# SBH_Charger_Main.net
KiCad netlist of a schematic drawn in Altium Designer
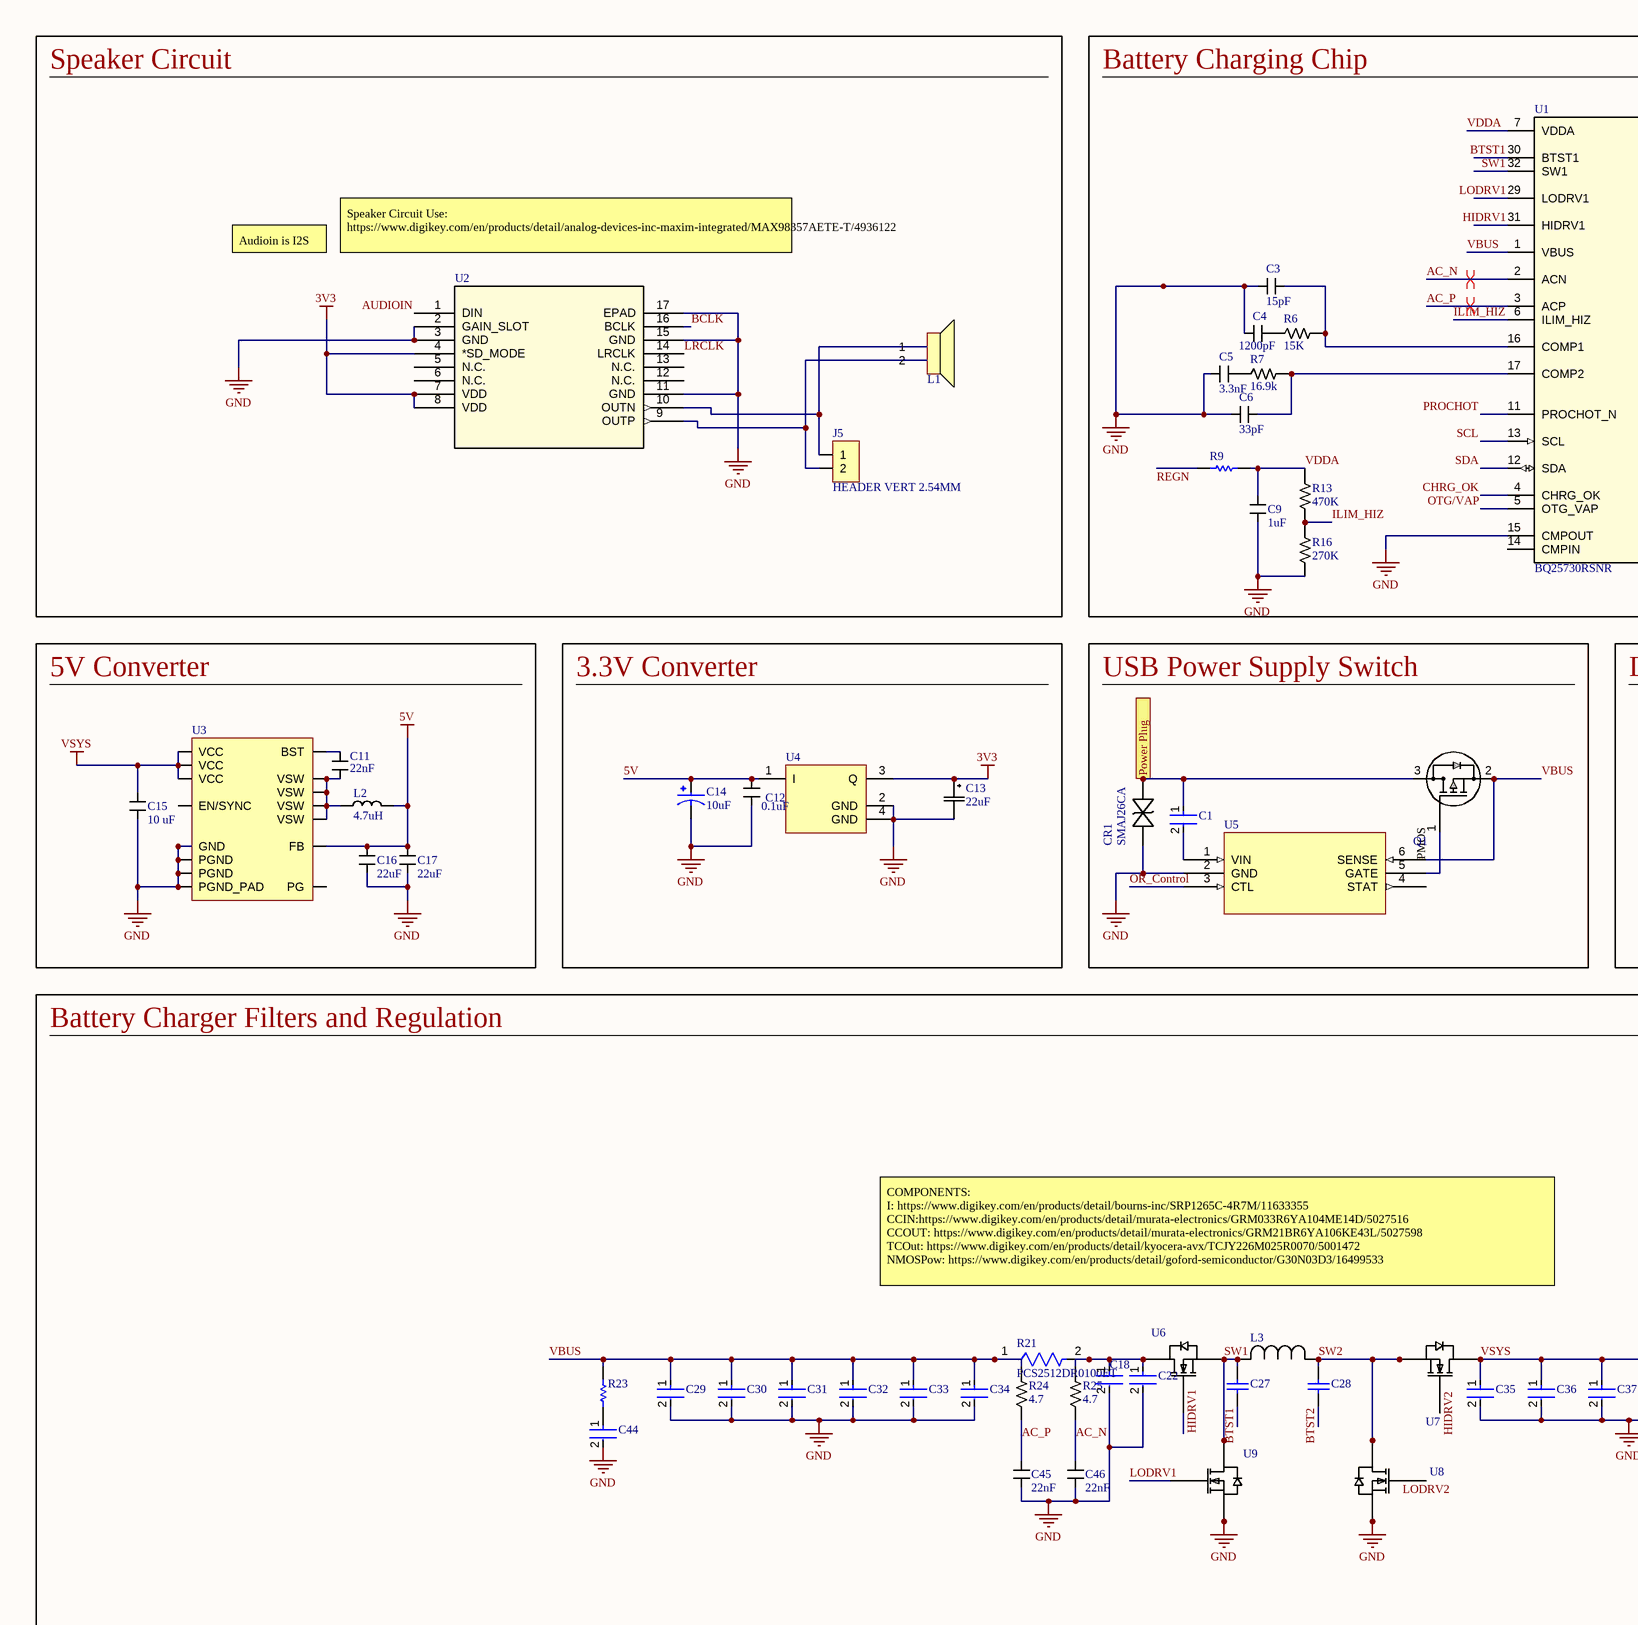
[diagram p0: SBH_Charger_Main.SchDoc, left]
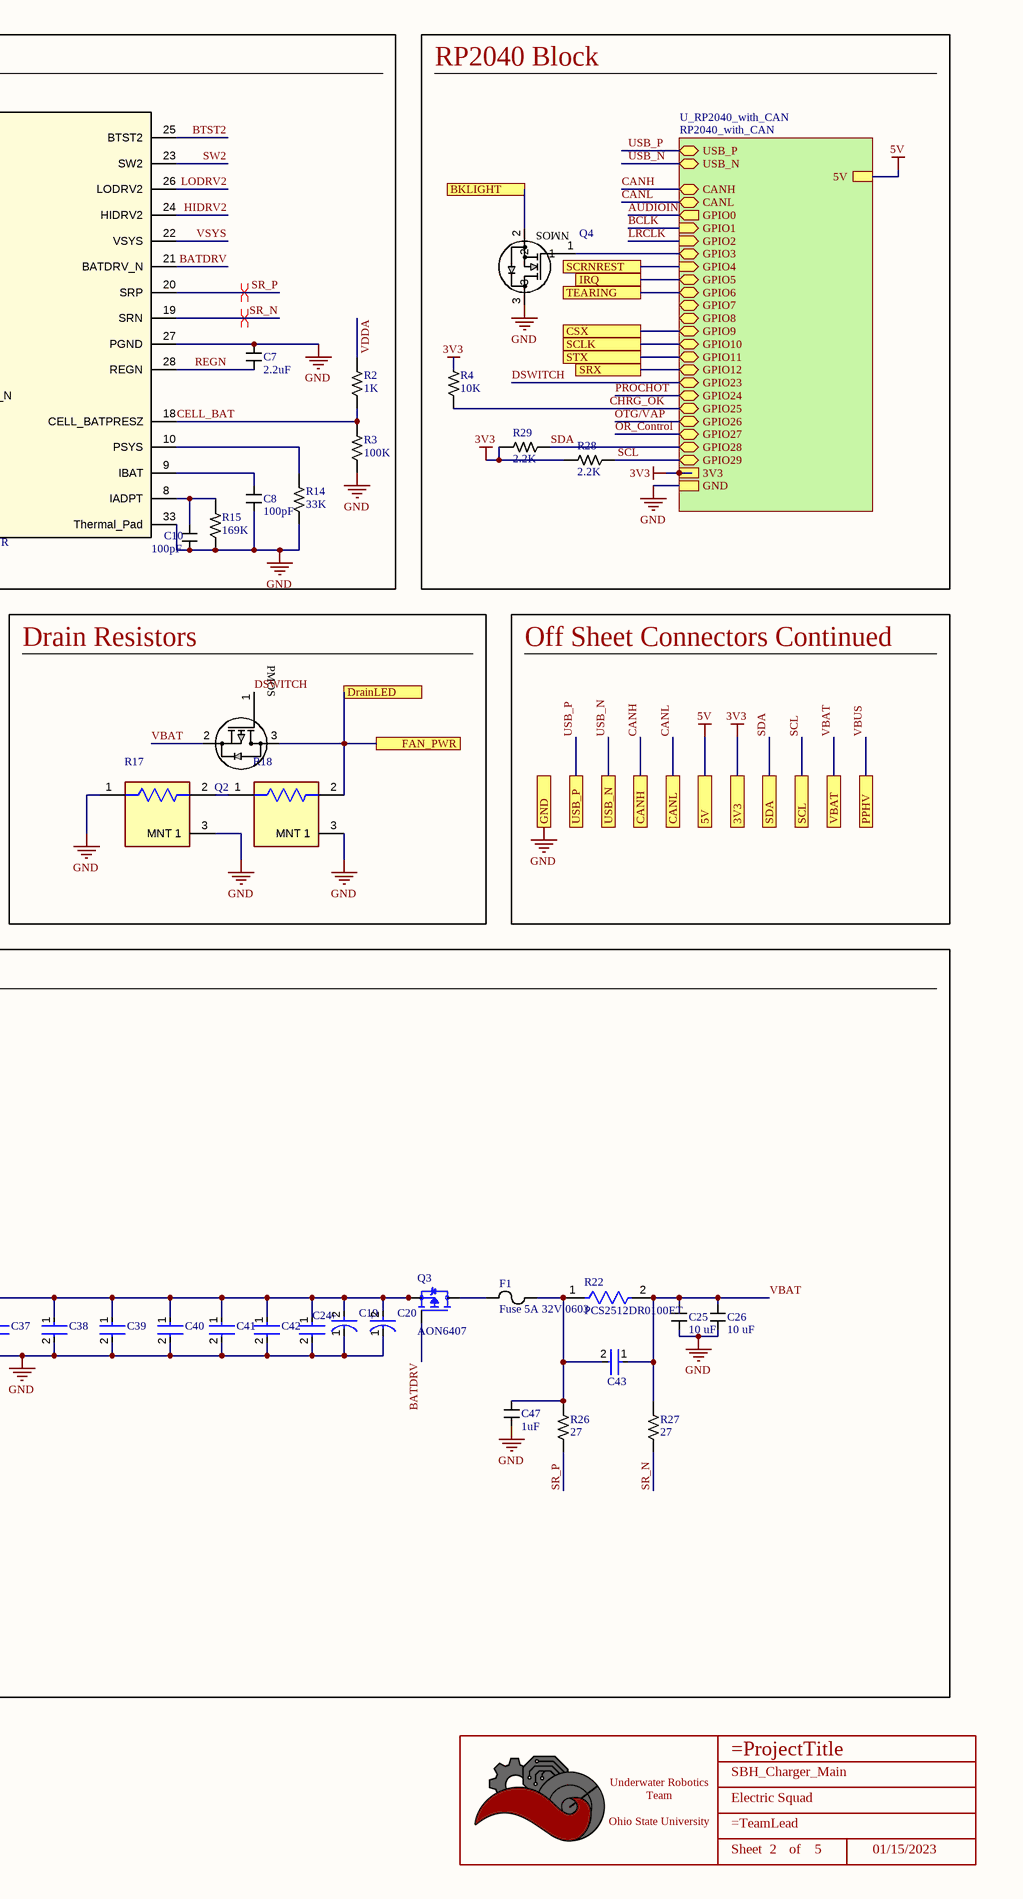
[diagram p1: SBH_Charger_Main.SchDoc, right]

(export (version "E")
  (design (tool "Eeschema 10.0.6"))
  (components
    (comp (ref "*")
      (value "Title_Block")
      (footprint "LOGO")
      (description "UWRT Schematic Title Block Template\r\n\r\nCreated June 2021, Dylan Trainor")
      (libsource (lib "UWRT") (part "Title_Block"))
    )
    (comp (ref "C1")
      (value "CC0402KRX7R9BB103")
      (footprint "CAPACITOR_0402")
      (description "CAP CER 10000PF 50V X7R 0402")
      (fields
        (field (name "OCTOPART") "https://octopart.com/cc0402krx7r9bb103-yageo-8376513")
        (field (name "MANUFACTURER") "YAGEO")
      )
      (libsource (lib "Capacitors") (part "CAP CER 0.01 UF 0402"))
    )
    (comp (ref "C3")
      (value "15pF")
      (footprint "CAPACITOR_0402")
      (description "CAP CER 15PF 50V C0G/NP0 0402")
      (fields (field (name "TOLERANCE") "+/- 5%") (field (name "VOLTAGE") "50V"))
      (libsource (lib "Capacitors") (part "CAPACITOR_0.000015uF_0402"))
    )
    (comp (ref "C4")
      (value "1200pF")
      (footprint "CAPACITOR_0402")
      (description "CAP CER 1200PF 50V X7R 0402")
      (fields (field (name "TOLERANCE") "+/- 5%") (field (name "VOLTAGE") "50V"))
      (libsource (lib "Capacitors") (part "CAPACITOR_0.0012uF_0402"))
    )
    (comp (ref "C5")
      (value "3.3nF")
      (footprint "CAPACITOR_0402")
      (description "CAP CER 3300PF 50V X7R 0402")
      (fields (field (name "TOLERANCE") "+/- 5%") (field (name "VOLTAGE") "50V"))
      (libsource (lib "Capacitors") (part "CAPACITOR_0.0033uF_0402"))
    )
    (comp (ref "C6")
      (value "33pF")
      (footprint "CAPACITOR_0402")
      (description "CAP CER 33PF 50V C0G/NP0 0402")
      (fields (field (name "TOLERANCE") "+/- 5%") (field (name "VOLTAGE") "50V"))
      (libsource (lib "Capacitors") (part "CAPACITOR_0.000033uF_0402"))
    )
    (comp (ref "C7")
      (value "2.2uF")
      (footprint "CAPACITOR_0402")
      (description "Cap 2.2uF 35V +/-10%\r\nCeramic 0402")
      (fields (field (name "TOLERANCE") "+/- 10%") (field (name "VOLTAGE") "35V"))
      (libsource (lib "Capacitors") (part "CAPACITOR_2.2uF_0402"))
    )
    (comp (ref "C8")
      (value "100pF")
      (footprint "CAPACITOR_0603")
      (description "CAP CER 100PF 50V C0G/NP0 0603")
      (fields (field (name "TOLERANCE") "+/- 5%") (field (name "VOLTAGE") "50V"))
      (libsource (lib "Capacitors") (part "CAPACITOR_0.0001uF_0603"))
    )
    (comp (ref "C9")
      (value "1uF")
      (footprint "CAPACITOR_0603")
      (description "Cap 1uF 16V +/-10%\r\nCeramic 0603")
      (fields (field (name "TOLERANCE") "+/- 10%") (field (name "VOLTAGE") "16V"))
      (libsource (lib "Capacitors") (part "CAPACITOR_1uF_0603"))
    )
    (comp (ref "C10")
      (value "100pF")
      (footprint "CAPACITOR_0603")
      (description "CAP CER 100PF 50V C0G/NP0 0603")
      (fields (field (name "TOLERANCE") "+/- 5%") (field (name "VOLTAGE") "50V"))
      (libsource (lib "Capacitors") (part "CAPACITOR_0.0001uF_0603"))
    )
    (comp (ref "C11")
      (value "22nF")
      (footprint "CAPACITOR_0402")
      (description "Cap 22nF 25V +/-10%\r\nCeramic 0402")
      (fields (field (name "TOLERANCE") "+/- 10%") (field (name "VOLTAGE") "25V"))
      (libsource (lib "Capacitors") (part "CAPACITOR_0.022uF_0402"))
    )
    (comp (ref "C12")
      (value "0.1uF")
      (footprint "CAPACITOR_0603")
      (description "Cap 100nF 25V +/-10%\r\nCeramic 0603")
      (fields (field (name "TOLERANCE") "+/- 10%") (field (name "VOLTAGE") "6.3V"))
      (libsource (lib "Capacitors") (part "CAPACITOR_0.1uF_0603_25V"))
    )
    (comp (ref "C13")
      (value "22uF")
      (footprint "PCAP_8x5.4-ELECT_NCA")
      (description "22 µF 35 V Aluminum Electrolytic Capacitors Radial, Can - SMD 1000 Hrs")
      (fields (field (name "VOLTAGE") "35V") (field (name "Comment") "22uF electrolytic 35 V"))
      (libsource (lib "Capacitors") (part "CAP ALUM 22UF 20% 35V SMD"))
    )
    (comp (ref "C14")
      (value "10uF")
      (footprint "CAP_EEHZC1J100P")
      (description "10 µF 63 V Aluminum - Polymer Capacitors Radial, Can SMD 120mOhm")
      (fields (field (name "TOLERANCE") "+/- 20%") (field (name "Comment") "10uF electrolytic 63V"))
      (libsource (lib "Capacitors") (part "CAP ALUM 10UF 20% 63V SMD"))
    )
    (comp (ref "C15")
      (value "10uF Ceramic 25V")
      (footprint "CAPACITOR_1206")
      (description "Cap 10uF 25V +/-10%\r\nCeramic 1206")
      (fields
        (field (name "TOLERANCE") "+/- 10%")
        (field (name "VOLTAGE") "25V")
        (field (name "VALUE (UF)") "10 uF")
      )
      (libsource (lib "Capacitors") (part "CAPACITOR_10uF_1206"))
    )
    (comp (ref "C16")
      (value "22uF")
      (footprint "CAPACITOR_0805")
      (description "Cap 22uF 10V +/-20% X5R\r\nCeramic 0805")
      (fields (field (name "TOLERANCE") "+/- 20%") (field (name "VOLTAGE") "10V"))
      (libsource (lib "Capacitors") (part "CAPACITOR_22uF_0805"))
    )
    (comp (ref "C17")
      (value "22uF")
      (footprint "CAPACITOR_0805")
      (description "Cap 22uF 10V +/-20% X5R\r\nCeramic 0805")
      (fields (field (name "TOLERANCE") "+/- 20%") (field (name "VOLTAGE") "10V"))
      (libsource (lib "Capacitors") (part "CAPACITOR_22uF_0805"))
    )
    (comp (ref "C18")
      (value "CC0402KRX7R9BB103")
      (footprint "FP-CC0402-MFG")
      (description "CAP CER 10000PF 50V X7R 0402")
      (fields
        (field (name "OCTOPART") "https://octopart.com/cc0402krx7r9bb103-yageo-8376513")
        (field (name "MANUFACTURER") "YAGEO")
      )
      (libsource (lib "Altium Content Vault") (part "11868f565c42a9108669ba33697ecf6"))
    )
    (comp (ref "C19")
      (value "TAJD226K035RNJ")
      (footprint "FP-TAJD-MFG")
      (description "22uF 35V  ±10% 900mΩ 2917  SMD Tantalum Capacitor")
      (fields (field (name "TOLERANCE") "10%") (field (name "VOLTAGE") "35V"))
      (libsource (lib "Altium Content Vault") (part "a00bbbee19879c290e62620ae7e47b1"))
    )
    (comp (ref "C20")
      (value "TAJD226K035RNJ")
      (footprint "FP-TAJD-MFG")
      (description "22uF 35V  ±10% 900mΩ 2917  SMD Tantalum Capacitor")
      (fields (field (name "TOLERANCE") "10%") (field (name "VOLTAGE") "35V"))
      (libsource (lib "Altium Content Vault") (part "a00bbbee19879c290e62620ae7e47b1"))
    )
    (comp (ref "C22")
      (value "C0402C102J5GACTU")
      (footprint "FP-C0402-BB-MFG")
      (description "CAP CER 1000PF 50V 5% NP0 0402")
      (fields
        (field (name "OCTOPART") "https://octopart.com/c0402c102j5gactu-kemet-9145103")
        (field (name "TOLERANCE") "0.05")
      )
      (libsource (lib "Altium Content Vault") (part "b4654b650e69147ec39a6b967a45e02"))
    )
    (comp (ref "C24")
      (value "C3216X7R1V106M160AC")
      (footprint "FP-C3216-160-0_2-IPC_C")
      (description "Multilayer Ceramic Capacitors 10uF ±20% 35V X7R SMD 1206")
      (fields (field (name "TOLERANCE") "20%"))
      (libsource (lib "Altium Content Vault") (part "11868f565c42a9108669ba33697ecf6"))
    )
    (comp (ref "C25")
      (value "10uF Ceramic 25V")
      (footprint "CAPACITOR_1206")
      (description "Cap 10uF 25V +/-10%\r\nCeramic 1206")
      (fields
        (field (name "TOLERANCE") "+/- 10%")
        (field (name "VOLTAGE") "25V")
        (field (name "VALUE (UF)") "10 uF")
      )
      (libsource (lib "Capacitors") (part "CAPACITOR_10uF_1206"))
    )
    (comp (ref "C26")
      (value "10uF Ceramic 25V")
      (footprint "CAPACITOR_1206")
      (description "Cap 10uF 25V +/-10%\r\nCeramic 1206")
      (fields
        (field (name "TOLERANCE") "+/- 10%")
        (field (name "VOLTAGE") "25V")
        (field (name "VALUE (UF)") "10 uF")
      )
      (libsource (lib "Capacitors") (part "CAPACITOR_10uF_1206"))
    )
    (comp (ref "C27")
      (value "GRM188R71H473KA61D")
      (footprint "CAPC1608X90X35ML10T15")
      (fields (field (name "MANUFACTURER") "Murata"))
      (libsource (lib "Altium Content Vault") (part "CAP"))
    )
    (comp (ref "C28")
      (value "GRM188R71H473KA61D")
      (footprint "CAPC1608X90X35ML10T15")
      (fields (field (name "MANUFACTURER") "Murata"))
      (libsource (lib "Altium Content Vault") (part "CAP"))
    )
    (comp (ref "C29")
      (value "C3216X7R1V106M160AC")
      (footprint "FP-C3216-160-0_2-IPC_C")
      (description "Multilayer Ceramic Capacitors 10uF ±20% 35V X7R SMD 1206")
      (fields (field (name "TOLERANCE") "20%"))
      (libsource (lib "Altium Content Vault") (part "11868f565c42a9108669ba33697ecf6"))
    )
    (comp (ref "C30")
      (value "C3216X7R1V106M160AC")
      (footprint "FP-C3216-160-0_2-IPC_C")
      (description "Multilayer Ceramic Capacitors 10uF ±20% 35V X7R SMD 1206")
      (fields (field (name "TOLERANCE") "20%"))
      (libsource (lib "Altium Content Vault") (part "11868f565c42a9108669ba33697ecf6"))
    )
    (comp (ref "C31")
      (value "C3216X7R1V106M160AC")
      (footprint "FP-C3216-160-0_2-IPC_C")
      (description "Multilayer Ceramic Capacitors 10uF ±20% 35V X7R SMD 1206")
      (fields (field (name "TOLERANCE") "20%"))
      (libsource (lib "Altium Content Vault") (part "11868f565c42a9108669ba33697ecf6"))
    )
    (comp (ref "C32")
      (value "C3216X7R1V106M160AC")
      (footprint "FP-C3216-160-0_2-IPC_C")
      (description "Multilayer Ceramic Capacitors 10uF ±20% 35V X7R SMD 1206")
      (fields (field (name "TOLERANCE") "20%"))
      (libsource (lib "Altium Content Vault") (part "11868f565c42a9108669ba33697ecf6"))
    )
    (comp (ref "C33")
      (value "C3216X7R1V106M160AC")
      (footprint "FP-C3216-160-0_2-IPC_C")
      (description "Multilayer Ceramic Capacitors 10uF ±20% 35V X7R SMD 1206")
      (fields (field (name "TOLERANCE") "20%"))
      (libsource (lib "Altium Content Vault") (part "11868f565c42a9108669ba33697ecf6"))
    )
    (comp (ref "C34")
      (value "C3216X7R1V106M160AC")
      (footprint "FP-C3216-160-0_2-IPC_C")
      (description "Multilayer Ceramic Capacitors 10uF ±20% 35V X7R SMD 1206")
      (fields (field (name "TOLERANCE") "20%"))
      (libsource (lib "Altium Content Vault") (part "11868f565c42a9108669ba33697ecf6"))
    )
    (comp (ref "C35")
      (value "C3216X7R1V106M160AC")
      (footprint "FP-C3216-160-0_2-IPC_C")
      (description "Multilayer Ceramic Capacitors 10uF ±20% 35V X7R SMD 1206")
      (fields (field (name "TOLERANCE") "20%"))
      (libsource (lib "Altium Content Vault") (part "11868f565c42a9108669ba33697ecf6"))
    )
    (comp (ref "C36")
      (value "C3216X7R1V106M160AC")
      (footprint "FP-C3216-160-0_2-IPC_C")
      (description "Multilayer Ceramic Capacitors 10uF ±20% 35V X7R SMD 1206")
      (fields (field (name "TOLERANCE") "20%"))
      (libsource (lib "Altium Content Vault") (part "11868f565c42a9108669ba33697ecf6"))
    )
    (comp (ref "C37")
      (value "C3216X7R1V106M160AC")
      (footprint "FP-C3216-160-0_2-IPC_C")
      (description "Multilayer Ceramic Capacitors 10uF ±20% 35V X7R SMD 1206")
      (fields (field (name "TOLERANCE") "20%"))
      (libsource (lib "Altium Content Vault") (part "11868f565c42a9108669ba33697ecf6"))
    )
    (comp (ref "C38")
      (value "C3216X7R1V106M160AC")
      (footprint "FP-C3216-160-0_2-IPC_C")
      (description "Multilayer Ceramic Capacitors 10uF ±20% 35V X7R SMD 1206")
      (fields (field (name "TOLERANCE") "20%"))
      (libsource (lib "Altium Content Vault") (part "11868f565c42a9108669ba33697ecf6"))
    )
    (comp (ref "C39")
      (value "C3216X7R1V106M160AC")
      (footprint "FP-C3216-160-0_2-IPC_C")
      (description "Multilayer Ceramic Capacitors 10uF ±20% 35V X7R SMD 1206")
      (fields (field (name "TOLERANCE") "20%"))
      (libsource (lib "Altium Content Vault") (part "11868f565c42a9108669ba33697ecf6"))
    )
    (comp (ref "C40")
      (value "C3216X7R1V106M160AC")
      (footprint "FP-C3216-160-0_2-IPC_C")
      (description "Multilayer Ceramic Capacitors 10uF ±20% 35V X7R SMD 1206")
      (fields (field (name "TOLERANCE") "20%"))
      (libsource (lib "Altium Content Vault") (part "11868f565c42a9108669ba33697ecf6"))
    )
    (comp (ref "C41")
      (value "C3216X7R1V106M160AC")
      (footprint "FP-C3216-160-0_2-IPC_C")
      (description "Multilayer Ceramic Capacitors 10uF ±20% 35V X7R SMD 1206")
      (fields (field (name "TOLERANCE") "20%"))
      (libsource (lib "Altium Content Vault") (part "11868f565c42a9108669ba33697ecf6"))
    )
    (comp (ref "C42")
      (value "C3216X7R1V106M160AC")
      (footprint "FP-C3216-160-0_2-IPC_C")
      (description "Multilayer Ceramic Capacitors 10uF ±20% 35V X7R SMD 1206")
      (fields (field (name "TOLERANCE") "20%"))
      (libsource (lib "Altium Content Vault") (part "11868f565c42a9108669ba33697ecf6"))
    )
    (comp (ref "C43")
      (value "GRM033R6YA104ME14D")
      (footprint "FP-GRM033-0_03-IPC_C")
      (description "Chip Multilayer Ceramic Capacitors for General Purpose, 0201, 0.10uF, X5R, 15%, 20%, 35V")
      (fields (field (name "TOLERANCE") "20%"))
      (libsource (lib "Capacitors") (part "CAPACITOR_0.1uF_0603_1"))
    )
    (comp (ref "C44")
      (value "UMK107AB7105KA-T")
      (footprint "FP-0603-L_1_6_0_15-W_0_8-IPC_C")
      (description "Ceramic Capacitor General Use 1uF ±10% 50V X7R 0603")
      (fields (field (name "TOLERANCE") "10%"))
      (libsource (lib "Altium Content Vault") (part "11868f565c42a9108669ba33697ecf6"))
    )
    (comp (ref "C45")
      (value "22nF")
      (footprint "CAPACITOR_0402")
      (description "Cap 22nF 25V +/-10%\r\nCeramic 0402")
      (fields (field (name "TOLERANCE") "+/- 10%") (field (name "VOLTAGE") "25V"))
      (libsource (lib "Capacitors") (part "CAPACITOR_0.022uF_0402"))
    )
    (comp (ref "C46")
      (value "22nF")
      (footprint "CAPACITOR_0402")
      (description "Cap 22nF 25V +/-10%\r\nCeramic 0402")
      (fields (field (name "TOLERANCE") "+/- 10%") (field (name "VOLTAGE") "25V"))
      (libsource (lib "Capacitors") (part "CAPACITOR_0.022uF_0402"))
    )
    (comp (ref "C47")
      (value "1uF")
      (footprint "CAPACITOR_0603")
      (description "Cap 1uF 16V +/-10%\r\nCeramic 0603")
      (fields (field (name "TOLERANCE") "+/- 10%") (field (name "VOLTAGE") "16V"))
      (libsource (lib "Capacitors") (part "CAPACITOR_1uF_0603"))
    )
    (comp (ref "CR1")
      (value "SMAJ26CA")
      (footprint "SMASeries_LTF")
      (description "TVS DIODE 26VWM 42.1VC DO214AC")
      (libsource (lib "Diodes") (part "TVS_SMAJ26CA"))
    )
    (comp (ref "F1")
      (value "Fuse 5A 32V 0603")
      (footprint "2-SMD Fuse 0603")
      (description "Pansonic ¦ 32V ¦ 5A ¦ 0603 ¦ Fast Blow")
      (fields (field (name "MANUFACTURER_PART_NUMBER") "ERB-RE5R00V"))
      (libsource (lib "Fuses") (part "ERB-RE5R00V"))
    )
    (comp (ref "J5")
      (value "HEADER VERT 2.54MM")
      (footprint "HEADER_2PIN_2.54MM")
      (description "CONN HEADER VERT 2POS 2.54MM")
      (libsource (lib "Connectors") (part "HEADER_2PIN_2.54MM"))
    )
    (comp (ref "L1")
      (value "SPEAKER_SP_1609S")
      (footprint "SPEAKER_SP-1609S")
      (description "8 Ohms General Purpose Speaker 700 mW 200 Hz ~ 5 kHz Top Rectangular")
      (libsource (lib "Inductors") (part "SPEAKER_SP_1609S"))
    )
    (comp (ref "L2")
      (value "4.7uH")
      (footprint "INDUCTOR_SLF7045")
      (description "4.7 µH Shielded Drum Core, Wirewound Inductor 2.1 A 36mOhm Max Nonstandard")
      (fields (field (name "TOLERANCE") "+/- 20%") (field (name "Comment") "4.7uH Shielded Drum Core"))
      (libsource (lib "Inductors") (part "INDUCTOR_4.7uH_SLF7045T"))
    )
    (comp (ref "L3")
      (value "SRP1770TA-3R3M")
      (footprint "INDUCTOR_SRP1770TA-3R3M_BRN")
      (description "3.3 µH Shielded Drum Core, Wirewound Inductor 28 A 3.9mOhm Max Nonstandard")
      (fields (field (name "MANUFACTURER_PART_NUMBER") "SRP1265C-4R7M"))
      (libsource (lib "Inductors") (part "INDUCTOR_3.3uH_SRP1770TA_3R3M"))
    )
    (comp (ref "Q1")
      (value "DMP3056L-7")
      (footprint "SOT-23-3")
      (description "P-Channel 30V 4.3A (Ta) 1.38W (Ta) Surface Mount SOT23")
      (libsource (lib "Transistors") (part "DMP3056L-7"))
    )
    (comp (ref "Q2")
      (value "DMP3056L-7")
      (footprint "SOT-23-3")
      (description "P-Channel 30V 4.3A (Ta) 1.38W (Ta) Surface Mount SOT23")
      (libsource (lib "Transistors") (part "DMP3056L-7"))
    )
    (comp (ref "Q3")
      (value "AON6407")
      (footprint "TRANS_AON6407")
      (description "P-Channel 30V 32A (Ta), 85A (Tc) 7.3W (Ta), 83W (Tc) Surface Mount 8-DFN (5x6)")
      (fields (field (name "DIGI-KEY_PART_NUMBER") "785-1421-1-ND") (field (name "MF") "Alpha &"))
      (libsource (lib "Transistors") (part "AON6407"))
    )
    (comp (ref "Q4")
      (value "MOSFET N-CH 30V 5.8A SOT-23-3")
      (footprint "SOT-23-3")
      (description "N-Channel 30 V 5.8A (Ta) 1.4W (Ta) Surface Mount SOT-23-3")
      (fields (field (name "MANUFACTURER _PART_NUMBER") "AO3404A"))
      (libsource (lib "Transistors") (part "AO3404A"))
    )
    (comp (ref "R2")
      (value "1k Ohm 5% 1/8W")
      (footprint "RESISTOR_0603")
      (description "RES 1k OHM 5% 1/8W 0603")
      (fields (field (name "TOLERANCE") "+/- 5%") (field (name "VALUE  (OHMS)") "1K"))
      (libsource (lib "Resistors") (part "RESISTOR_1K_0603"))
    )
    (comp (ref "R3")
      (value "100k Ohm 5% 1/8W")
      (footprint "RESISTOR_0603")
      (description "RES 100k OHM 5% 1/10W 0603")
      (fields (field (name "TOLERANCE") "+/- 5%") (field (name "VALUE  (OHMS)") "100K"))
      (libsource (lib "Resistors") (part "RESISTOR_100K_0603"))
    )
    (comp (ref "R4")
      (value "10k Ohm 5% 1/10W")
      (footprint "RESISTOR_0603")
      (description "RES 10k OHM 5% 1/10W 0603")
      (fields (field (name "TOLERANCE") "+/- 5%") (field (name "VALUE  (OHMS)") "10K"))
      (libsource (lib "Resistors") (part "RESISTOR_10K_0603"))
    )
    (comp (ref "R6")
      (value "15k Ohm 5% 1/10W")
      (footprint "RESISTOR_0603")
      (description "RES 15k OHM 5% 1/10W 0603")
      (fields (field (name "TOLERANCE") "+/- 5%") (field (name "VALUE  (OHMS)") "15K"))
      (libsource (lib "Resistors") (part "RESISTOR_15K_0603"))
    )
    (comp (ref "R7")
      (value "16.9k Ohm 1% 1/16W")
      (footprint "RESISTOR_0402")
      (description "16.9 kOhms ±1% 0.063W, 1/16W Chip Resistor 0402 (1005 Metric) Moisture Resistant Thick Film")
      (fields (field (name "TOLERANCE") "+/- 1%") (field (name "VALUE  (OHMS)") "16.9k"))
      (libsource (lib "Resistors") (part "RESISTOR_16.9K_0402"))
    )
    (comp (ref "R9")
      (value "CRCW040210R0FKEDHP")
      (footprint "RESC1005X40X25NL05T10")
      (fields (field (name "MANUFACTURER") "Vishay Dale"))
      (libsource (lib "Altium Content Vault") (part "RES"))
    )
    (comp (ref "R13")
      (value "470k Ohm 5% 1/10W")
      (footprint "RESISTOR_0603")
      (description "RES 470k OHM 5% 1/10W 0603")
      (fields (field (name "TOLERANCE") "+/- 5%") (field (name "VALUE  (OHMS)") "470K"))
      (libsource (lib "Resistors") (part "RESISTOR_470K_0603"))
    )
    (comp (ref "R14")
      (value "33k Ohm 5% 1/8W")
      (footprint "RESISTOR_0805")
      (description "RES 33k OHM 5% 1/8W 0805")
      (fields (field (name "TOLERANCE") "+/- 5%") (field (name "VALUE  (OHMS)") "33K"))
      (libsource (lib "Resistors") (part "RESISTOR_33K_0805"))
    )
    (comp (ref "R15")
      (value "169K OHM 1% 1/3W")
      (footprint "RESISTOR_0603")
      (fields (field (name "TOLERANCE") "+/- 1%") (field (name "VALUE  (OHMS)") "169K"))
      (libsource (lib "Resistors") (part "RESISTOR_169K_1%_0603"))
    )
    (comp (ref "R16")
      (value "270k Ohm 1% 1/10W")
      (footprint "RESISTOR_0603")
      (description "RES 270k OHM 1% 1/10W 0603")
      (fields (field (name "TOLERANCE") "+/- 1%") (field (name "VALUE  (OHMS)") "270K"))
      (libsource (lib "Resistors") (part "RESISTOR_270K_1%_0603"))
    )
    (comp (ref "R17")
      (value "PWR163S-25-10R0JE")
      (footprint "FP-PWR163-MFG")
      (description "RES SMD 10 OHM 5% 25W DPAK")
      (libsource (lib "Resistors") (part "PWR163S-25-10R0JE"))
    )
    (comp (ref "R18")
      (value "PWR163S-25-10R0JE")
      (footprint "FP-PWR163-MFG")
      (description "RES SMD 10 OHM 5% 25W DPAK")
      (libsource (lib "Resistors") (part "PWR163S-25-10R0JE"))
    )
    (comp (ref "R21")
      (value "PCS2512DR0100ET")
      (footprint "FP-PCS2512-MFG")
      (description "2W 0.010 OHMS 0.5% 2512")
      (fields
        (field (name "OCTOPART") "https://octopart.com/pcs2512dr0100et-ohmite-106082038")
        (field (name "TOLERANCE") "0.%")
      )
      (libsource (lib "Altium Content Vault") (part "1029c3af85768c4190bb7ad29bc67b5"))
    )
    (comp (ref "R22")
      (value "PCS2512DR0100ET")
      (footprint "FP-PCS2512-MFG")
      (description "2W 0.010 OHMS 0.5% 2512")
      (fields
        (field (name "OCTOPART") "https://octopart.com/pcs2512dr0100et-ohmite-106082038")
        (field (name "TOLERANCE") "0.%")
      )
      (libsource (lib "Altium Content Vault") (part "1029c3af85768c4190bb7ad29bc67b5"))
    )
    (comp (ref "R23")
      (value "CRCW06032R20FKEA")
      (footprint "RESC1609X50X30ML10T20")
      (fields (field (name "MANUFACTURER") "Vishay Dale"))
      (libsource (lib "Altium Content Vault") (part "RES"))
    )
    (comp (ref "R24")
      (value "4.7 Ohm 5% 1/8W")
      (footprint "RESISTOR_0603")
      (description "RES 4.7 OHM 5% 1/8W 0603")
      (fields (field (name "TOLERANCE") "+/- 5%") (field (name "VALUE  (OHMS)") "4.7"))
      (libsource (lib "Resistors") (part "RESISTOR_4.7_0603"))
    )
    (comp (ref "R25")
      (value "4.7 Ohm 5% 1/8W")
      (footprint "RESISTOR_0603")
      (description "RES 4.7 OHM 5% 1/8W 0603")
      (fields (field (name "TOLERANCE") "+/- 5%") (field (name "VALUE  (OHMS)") "4.7"))
      (libsource (lib "Resistors") (part "RESISTOR_4.7_0603"))
    )
    (comp (ref "R26")
      (value "27 Ohm 5% 1/8W")
      (footprint "RESISTOR_0603")
      (description "RES 27 OHM 5% 1/8W 0603")
      (fields (field (name "TOLERANCE") "+/- 5%") (field (name "VALUE  (OHMS)") "27"))
      (libsource (lib "Resistors") (part "RESISTOR_27_0603"))
    )
    (comp (ref "R27")
      (value "27 Ohm 5% 1/8W")
      (footprint "RESISTOR_0603")
      (description "RES 27 OHM 5% 1/8W 0603")
      (fields (field (name "TOLERANCE") "+/- 5%") (field (name "VALUE  (OHMS)") "27"))
      (libsource (lib "Resistors") (part "RESISTOR_27_0603"))
    )
    (comp (ref "R28")
      (value "2.2k Ohm 1% 1/16W")
      (footprint "RESISTOR_0402")
      (description "RES 2.2K OHM 1% 1/16W 0402")
      (fields (field (name "TOLERANCE") "+/- 1%") (field (name "VALUE  (OHMS)") "2.2K"))
      (libsource (lib "Resistors") (part "RESISTOR_2.2K_0402_1"))
    )
    (comp (ref "R29")
      (value "2.2k Ohm 1% 1/16W")
      (footprint "RESISTOR_0402")
      (description "RES 2.2K OHM 1% 1/16W 0402")
      (fields (field (name "TOLERANCE") "+/- 1%") (field (name "VALUE  (OHMS)") "2.2K"))
      (libsource (lib "Resistors") (part "RESISTOR_2.2K_0402_1"))
    )
    (comp (ref "U1")
      (value "BQ25730RSNR")
      (footprint "RSN0032B-IPC_B")
      (description "I2C 1 TO 5 CELL, 2-V, NARROW VDC, Charger IC Multi-Chemistry 32-QFN (4x4)")
      (libsource (lib "Integrated Circuits") (part "BQ25730RSNR"))
    )
    (comp (ref "U2")
      (value "MAX98357AETE+T")
      (footprint "TQFN-16")
      (description "Audio Amplifiers Digital Input Class D Amplifier")
      (libsource (lib "Integrated Circuits") (part "MAX98357AETE+T"))
    )
    (comp (ref "U3")
      (value "REG BUCK 5V 1A")
      (footprint "QFN-16 (3x3)")
      (description "Buck Switching Regulator IC Positive Fixed 5V 1 Output 1A 16-VFQFN Exposed Pad")
      (libsource (lib "Integrated Circuits") (part "TS30041-M050QFNR"))
    )
    (comp (ref "U4")
      (value "TLE42744GS V33")
      (footprint "INF-PG-SOT223_SC-73_N")
      (fields (field (name "MANUFACTURER") "Infineon"))
      (libsource (lib "Integrated Circuits") (part "CMP-1109-00085-1"))
    )
    (comp (ref "U5")
      (value "LTC4412ES6TRPBF")
      (footprint "TSOT-23_S6")
      (description "OR Controller Source Selector Switch P-Channel 2:1 TSOT-23-6")
      (fields (field (name "MP") "LTC4412ES6#TRPBF") (field (name "MF") "Analog Devices"))
      (libsource (lib "Integrated Circuits") (part "LTC4412ES6TRPBF"))
    )
    (comp (ref "U6")
      (value "G30N03D3")
      (footprint "DNH0008A_NV")
      (description "N-Channel 30 V 30A 24W Surface Mount 8-DFN (3.15x3.05)")
      (libsource (lib "Transistors") (part "G30N03D3"))
    )
    (comp (ref "U7")
      (value "G30N03D3")
      (footprint "DNH0008A_NV")
      (description "N-Channel 30 V 30A 24W Surface Mount 8-DFN (3.15x3.05)")
      (libsource (lib "Transistors") (part "G30N03D3"))
    )
    (comp (ref "U8")
      (value "G30N03D3")
      (footprint "DNH0008A_NV")
      (description "N-Channel 30 V 30A 24W Surface Mount 8-DFN (3.15x3.05)")
      (libsource (lib "Transistors") (part "G30N03D3"))
    )
    (comp (ref "U9")
      (value "G30N03D3")
      (footprint "DNH0008A_NV")
      (description "N-Channel 30 V 30A 24W Surface Mount 8-DFN (3.15x3.05)")
      (libsource (lib "Transistors") (part "G30N03D3"))
    )
  )
  (nets
    (net (code "2") (name "/AC_N") (class "Default")
      (node (ref "C46") (pin "1") (pinfunction "1_1") (pintype "passive"))
      (node (ref "R25") (pin "2") (pinfunction "2_2") (pintype "passive"))
      (node (ref "U1") (pin "2") (pinfunction "ACN_2") (pintype "passive"))
    )
    (net (code "3") (name "/AC_P") (class "Default")
      (node (ref "C45") (pin "1") (pinfunction "1_1") (pintype "passive"))
      (node (ref "R24") (pin "2") (pinfunction "2_2") (pintype "passive"))
      (node (ref "U1") (pin "3") (pinfunction "ACP_3") (pintype "passive"))
    )
    (net (code "4") (name "/AUDIOIN") (class "Default")
      (node (ref "U2") (pin "1") (pinfunction "DIN_1") (pintype "passive"))
    )
    (net (code "5") (name "/BATDRV") (class "Default")
      (node (ref "Q3") (pin "4") (pinfunction "G_4") (pintype "passive"))
      (node (ref "U1") (pin "21") (pinfunction "BATDRV_N_21") (pintype "passive"))
    )
    (net (code "6") (name "/BCLK") (class "Default")
      (node (ref "U2") (pin "16") (pinfunction "BCLK_16") (pintype "passive"))
    )
    (net (code "7") (name "/BKLIGHT") (class "Default")
      (node (ref "Q4") (pin "2") (pinfunction "2_2") (pintype "passive"))
    )
    (net (code "8") (name "/BTST1") (class "Default")
      (node (ref "C27") (pin "1") (pinfunction "1_1") (pintype "passive"))
      (node (ref "U1") (pin "30") (pinfunction "BTST1_30") (pintype "passive"))
    )
    (net (code "9") (name "/BTST2") (class "Default")
      (node (ref "C28") (pin "1") (pinfunction "1_1") (pintype "passive"))
      (node (ref "U1") (pin "25") (pinfunction "BTST2_25") (pintype "passive"))
    )
    (net (code "12") (name "/CELL_BAT") (class "Default")
      (node (ref "R2") (pin "2") (pinfunction "2_2") (pintype "passive"))
      (node (ref "R3") (pin "1") (pinfunction "1_1") (pintype "passive"))
      (node (ref "U1") (pin "18") (pinfunction "CELL_BATPRESZ_18") (pintype "passive"))
    )
    (net (code "13") (name "/CHRG_OK") (class "Default")
      (node (ref "R4") (pin "2") (pinfunction "2_2") (pintype "passive"))
      (node (ref "U1") (pin "4") (pinfunction "CHRG_OK_4") (pintype "passive"))
    )
    (net (code "15") (name "/DSWITCH") (class "Default")
      (node (ref "Q2") (pin "1") (pinfunction "1_1") (pintype "passive"))
    )
    (net (code "16") (name "/DrainLED") (class "Default")
      (node (ref "Q2") (pin "3") (pinfunction "3_3") (pintype "passive"))
      (node (ref "R18") (pin "2") (pinfunction "2_2") (pintype "passive"))
    )
    (net (code "17") (name "/GPIO3") (class "Default")
      (node (ref "Q4") (pin "1") (pinfunction "1_1") (pintype "passive"))
    )
    (net (code "20") (name "/HIDRV1") (class "Default")
      (node (ref "U1") (pin "31") (pinfunction "HIDRV1_31") (pintype "passive"))
      (node (ref "U6") (pin "4") (pinfunction "G_4") (pintype "passive"))
    )
    (net (code "21") (name "/HIDRV2") (class "Default")
      (node (ref "U1") (pin "24") (pinfunction "HIDRV2_24") (pintype "passive"))
      (node (ref "U7") (pin "4") (pinfunction "G_4") (pintype "passive"))
    )
    (net (code "22") (name "/ILIM_HIZ") (class "Default")
      (node (ref "R13") (pin "2") (pinfunction "2_2") (pintype "passive"))
      (node (ref "R16") (pin "1") (pinfunction "1_1") (pintype "passive"))
      (node (ref "U1") (pin "6") (pinfunction "ILIM_HIZ_6") (pintype "passive"))
    )
    (net (code "24") (name "/LODRV1") (class "Default")
      (node (ref "U1") (pin "29") (pinfunction "LODRV1_29") (pintype "passive"))
      (node (ref "U9") (pin "4") (pinfunction "G_4") (pintype "passive"))
    )
    (net (code "25") (name "/LODRV2") (class "Default")
      (node (ref "U1") (pin "26") (pinfunction "LODRV2_26") (pintype "passive"))
      (node (ref "U8") (pin "4") (pinfunction "G_4") (pintype "passive"))
    )
    (net (code "26") (name "/LRCLK") (class "Default")
      (node (ref "U2") (pin "14") (pinfunction "LRCLK_14") (pintype "passive"))
    )
    (net (code "27") (name "/OR_Control") (class "Default")
      (node (ref "U5") (pin "3") (pinfunction "CTL_3") (pintype "input"))
    )
    (net (code "28") (name "/OTG{slash}VAP") (class "Default")
      (node (ref "U1") (pin "5") (pinfunction "OTG_VAP_5") (pintype "passive"))
    )
    (net (code "29") (name "/PROCHOT") (class "Default")
      (node (ref "U1") (pin "11") (pinfunction "PROCHOT_N_11") (pintype "passive"))
    )
    (net (code "30") (name "/Power Plug") (class "Default")
      (node (ref "C1") (pin "1") (pinfunction "1_1") (pintype "passive"))
      (node (ref "CR1") (pin "1") (pinfunction "1_1") (pintype "passive"))
      (node (ref "Q1") (pin "3") (pinfunction "3_3") (pintype "passive"))
    )
    (net (code "31") (name "/REGN") (class "Default")
      (node (ref "C7") (pin "2") (pinfunction "2_2") (pintype "passive"))
      (node (ref "R9") (pin "1") (pinfunction "1_1") (pintype "passive"))
      (node (ref "U1") (pin "28") (pinfunction "REGN_28") (pintype "passive"))
    )
    (net (code "32") (name "/SCL") (class "Default")
      (node (ref "R28") (pin "2") (pinfunction "2_2") (pintype "passive"))
      (node (ref "U1") (pin "13") (pinfunction "SCL_13") (pintype "input"))
    )
    (net (code "35") (name "/SDA") (class "Default")
      (node (ref "R29") (pin "2") (pinfunction "2_2") (pintype "passive"))
      (node (ref "U1") (pin "12") (pinfunction "SDA_12") (pintype "bidirectional"))
    )
    (net (code "37") (name "/SR_N") (class "Default")
      (node (ref "R27") (pin "2") (pinfunction "2_2") (pintype "passive"))
      (node (ref "U1") (pin "19") (pinfunction "SRN_19") (pintype "passive"))
    )
    (net (code "38") (name "/SR_P") (class "Default")
      (node (ref "R26") (pin "2") (pinfunction "2_2") (pintype "passive"))
      (node (ref "U1") (pin "20") (pinfunction "SRP_20") (pintype "passive"))
    )
    (net (code "40") (name "/SW1") (class "Default")
      (node (ref "C27") (pin "2") (pinfunction "2_2") (pintype "passive"))
      (node (ref "L3") (pin "2") (pinfunction "2_2") (pintype "passive"))
      (node (ref "U1") (pin "32") (pinfunction "SW1_32") (pintype "passive"))
      (node (ref "U6") (pin "1") (pinfunction "S_1") (pintype "passive"))
      (node (ref "U6") (pin "2") (pinfunction "S_2") (pintype "passive"))
      (node (ref "U6") (pin "3") (pinfunction "S_3") (pintype "passive"))
      (node (ref "U9") (pin "5") (pinfunction "D_5") (pintype "passive"))
      (node (ref "U9") (pin "6") (pinfunction "D_6") (pintype "passive"))
      (node (ref "U9") (pin "7") (pinfunction "D_7") (pintype "passive"))
      (node (ref "U9") (pin "8") (pinfunction "D_8") (pintype "passive"))
      (node (ref "U9") (pin "9") (pinfunction "D_9") (pintype "passive"))
    )
    (net (code "41") (name "/SW2") (class "Default")
      (node (ref "C28") (pin "2") (pinfunction "2_2") (pintype "passive"))
      (node (ref "L3") (pin "1") (pinfunction "1_1") (pintype "passive"))
      (node (ref "U1") (pin "23") (pinfunction "SW2_23") (pintype "passive"))
      (node (ref "U7") (pin "1") (pinfunction "S_1") (pintype "passive"))
      (node (ref "U7") (pin "2") (pinfunction "S_2") (pintype "passive"))
      (node (ref "U7") (pin "3") (pinfunction "S_3") (pintype "passive"))
      (node (ref "U8") (pin "5") (pinfunction "D_5") (pintype "passive"))
      (node (ref "U8") (pin "6") (pinfunction "D_6") (pintype "passive"))
      (node (ref "U8") (pin "7") (pinfunction "D_7") (pintype "passive"))
      (node (ref "U8") (pin "8") (pinfunction "D_8") (pintype "passive"))
      (node (ref "U8") (pin "9") (pinfunction "D_9") (pintype "passive"))
    )
    (net (code "45") (name "/VBAT") (class "Default")
      (node (ref "C25") (pin "1") (pinfunction "1_1") (pintype "passive"))
      (node (ref "C26") (pin "1") (pinfunction "1_1") (pintype "passive"))
      (node (ref "C43") (pin "1") (pinfunction "1_1") (pintype "passive"))
      (node (ref "Q2") (pin "2") (pinfunction "2_2") (pintype "passive"))
      (node (ref "R22") (pin "2") (pinfunction "2_2") (pintype "passive"))
      (node (ref "R27") (pin "1") (pinfunction "1_1") (pintype "passive"))
    )
    (net (code "46") (name "/VBUS") (class "Default")
      (node (ref "C29") (pin "1") (pinfunction "1_1") (pintype "passive"))
      (node (ref "C30") (pin "1") (pinfunction "1_1") (pintype "passive"))
      (node (ref "C31") (pin "1") (pinfunction "1_1") (pintype "passive"))
      (node (ref "C32") (pin "1") (pinfunction "1_1") (pintype "passive"))
      (node (ref "C33") (pin "1") (pinfunction "1_1") (pintype "passive"))
      (node (ref "C34") (pin "1") (pinfunction "1_1") (pintype "passive"))
      (node (ref "Q1") (pin "2") (pinfunction "2_2") (pintype "passive"))
      (node (ref "R21") (pin "1") (pinfunction "1_1") (pintype "passive"))
      (node (ref "R23") (pin "2") (pinfunction "2_2") (pintype "passive"))
      (node (ref "R24") (pin "1") (pinfunction "1_1") (pintype "passive"))
      (node (ref "U1") (pin "1") (pinfunction "VBUS_1") (pintype "power_in"))
      (node (ref "U5") (pin "6") (pinfunction "SENSE_6") (pintype "input"))
    )
    (net (code "47") (name "/VDDA") (class "Default")
      (node (ref "C9") (pin "1") (pinfunction "1_1") (pintype "passive"))
      (node (ref "R13") (pin "1") (pinfunction "1_1") (pintype "passive"))
      (node (ref "R2") (pin "1") (pinfunction "1_1") (pintype "passive"))
      (node (ref "R9") (pin "2") (pinfunction "2_2") (pintype "passive"))
      (node (ref "U1") (pin "7") (pinfunction "VDDA_7") (pintype "power_in"))
    )
    (net (code "48") (name "3V3") (class "Default")
      (node (ref "C13") (pin "1") (pinfunction "1_1") (pintype "passive"))
      (node (ref "R28") (pin "1") (pinfunction "1_1") (pintype "passive"))
      (node (ref "R29") (pin "1") (pinfunction "1_1") (pintype "passive"))
      (node (ref "R4") (pin "1") (pinfunction "1_1") (pintype "passive"))
      (node (ref "U2") (pin "4") (pinfunction "*SD_MODE_4") (pintype "passive"))
      (node (ref "U2") (pin "7") (pinfunction "VDD_7") (pintype "power_in"))
      (node (ref "U2") (pin "8") (pinfunction "VDD_8") (pintype "power_in"))
      (node (ref "U4") (pin "3") (pinfunction "Q_3") (pintype "power_in"))
    )
    (net (code "49") (name "5V") (class "Default")
      (node (ref "C12") (pin "1") (pinfunction "1_1") (pintype "passive"))
      (node (ref "C14") (pin "1") (pinfunction "1_1") (pintype "passive"))
      (node (ref "C16") (pin "1") (pinfunction "1_1") (pintype "passive"))
      (node (ref "C17") (pin "1") (pinfunction "1_1") (pintype "passive"))
      (node (ref "L2") (pin "1") (pinfunction "1_1") (pintype "passive"))
      (node (ref "U3") (pin "5") (pinfunction "FB_5") (pintype "passive"))
      (node (ref "U4") (pin "1") (pinfunction "I_1") (pintype "power_in"))
    )
    (net (code "50") (name "GND") (class "Default")
      (node (ref "C10") (pin "2") (pinfunction "2_2") (pintype "passive"))
      (node (ref "C12") (pin "2") (pinfunction "2_2") (pintype "passive"))
      (node (ref "C13") (pin "2") (pinfunction "2_2") (pintype "passive"))
      (node (ref "C14") (pin "2") (pinfunction "2_2") (pintype "passive"))
      (node (ref "C15") (pin "2") (pinfunction "2_2") (pintype "passive"))
      (node (ref "C16") (pin "2") (pinfunction "2_2") (pintype "passive"))
      (node (ref "C17") (pin "2") (pinfunction "2_2") (pintype "passive"))
      (node (ref "C18") (pin "2") (pinfunction "2_2") (pintype "passive"))
      (node (ref "C19") (pin "1") (pinfunction "C_1") (pintype "passive"))
      (node (ref "C20") (pin "1") (pinfunction "C_1") (pintype "passive"))
      (node (ref "C22") (pin "2") (pinfunction "2_2") (pintype "passive"))
      (node (ref "C24") (pin "2") (pinfunction "2_2") (pintype "passive"))
      (node (ref "C25") (pin "2") (pinfunction "2_2") (pintype "passive"))
      (node (ref "C26") (pin "2") (pinfunction "2_2") (pintype "passive"))
      (node (ref "C29") (pin "2") (pinfunction "2_2") (pintype "passive"))
      (node (ref "C3") (pin "2") (pinfunction "2_2") (pintype "passive"))
      (node (ref "C30") (pin "2") (pinfunction "2_2") (pintype "passive"))
      (node (ref "C31") (pin "2") (pinfunction "2_2") (pintype "passive"))
      (node (ref "C32") (pin "2") (pinfunction "2_2") (pintype "passive"))
      (node (ref "C33") (pin "2") (pinfunction "2_2") (pintype "passive"))
      (node (ref "C34") (pin "2") (pinfunction "2_2") (pintype "passive"))
      (node (ref "C35") (pin "2") (pinfunction "2_2") (pintype "passive"))
      (node (ref "C36") (pin "2") (pinfunction "2_2") (pintype "passive"))
      (node (ref "C37") (pin "2") (pinfunction "2_2") (pintype "passive"))
      (node (ref "C38") (pin "2") (pinfunction "2_2") (pintype "passive"))
      (node (ref "C39") (pin "2") (pinfunction "2_2") (pintype "passive"))
      (node (ref "C4") (pin "2") (pinfunction "2_2") (pintype "passive"))
      (node (ref "C40") (pin "2") (pinfunction "2_2") (pintype "passive"))
      (node (ref "C41") (pin "2") (pinfunction "2_2") (pintype "passive"))
      (node (ref "C42") (pin "2") (pinfunction "2_2") (pintype "passive"))
      (node (ref "C44") (pin "2") (pinfunction "2_2") (pintype "passive"))
      (node (ref "C45") (pin "2") (pinfunction "2_2") (pintype "passive"))
      (node (ref "C46") (pin "2") (pinfunction "2_2") (pintype "passive"))
      (node (ref "C47") (pin "1") (pinfunction "1_1") (pintype "passive"))
      (node (ref "C5") (pin "2") (pinfunction "2_2") (pintype "passive"))
      (node (ref "C6") (pin "2") (pinfunction "2_2") (pintype "passive"))
      (node (ref "C7") (pin "1") (pinfunction "1_1") (pintype "passive"))
      (node (ref "C8") (pin "2") (pinfunction "2_2") (pintype "passive"))
      (node (ref "C9") (pin "2") (pinfunction "2_2") (pintype "passive"))
      (node (ref "CR1") (pin "2") (pinfunction "2_2") (pintype "passive"))
      (node (ref "Q4") (pin "3") (pinfunction "3_3") (pintype "passive"))
      (node (ref "R14") (pin "2") (pinfunction "2_2") (pintype "passive"))
      (node (ref "R15") (pin "2") (pinfunction "2_2") (pintype "passive"))
      (node (ref "R16") (pin "2") (pinfunction "2_2") (pintype "passive"))
      (node (ref "R17") (pin "1") (pinfunction "1_1") (pintype "passive"))
      (node (ref "R17") (pin "3") (pinfunction "MNT_1_3") (pintype "passive"))
      (node (ref "R18") (pin "3") (pinfunction "MNT_1_3") (pintype "passive"))
      (node (ref "R3") (pin "2") (pinfunction "2_2") (pintype "passive"))
      (node (ref "U1") (pin "15") (pinfunction "CMPOUT_15") (pintype "passive"))
      (node (ref "U1") (pin "27") (pinfunction "PGND_27") (pintype "power_in"))
      (node (ref "U1") (pin "33") (pinfunction "Thermal_Pad_33") (pintype "passive"))
      (node (ref "U2") (pin "11") (pinfunction "GND_11") (pintype "power_in"))
      (node (ref "U2") (pin "15") (pinfunction "GND_15") (pintype "power_in"))
      (node (ref "U2") (pin "17") (pinfunction "EPAD_17") (pintype "passive"))
      (node (ref "U2") (pin "2") (pinfunction "GAIN_SLOT_2") (pintype "passive"))
      (node (ref "U2") (pin "3") (pinfunction "GND_3") (pintype "power_in"))
      (node (ref "U3") (pin "14") (pinfunction "PGND_14") (pintype "power_in"))
      (node (ref "U3") (pin "15") (pinfunction "PGND_15") (pintype "power_in"))
      (node (ref "U3") (pin "17") (pinfunction "PGND_PAD_17") (pintype "power_in"))
      (node (ref "U3") (pin "4") (pinfunction "GND_4") (pintype "power_in"))
      (node (ref "U4") (pin "2") (pinfunction "GND_2") (pintype "power_in"))
      (node (ref "U4") (pin "4") (pinfunction "GND_4") (pintype "power_in"))
      (node (ref "U5") (pin "2") (pinfunction "GND_2") (pintype "power_in"))
      (node (ref "U8") (pin "1") (pinfunction "S_1") (pintype "passive"))
      (node (ref "U8") (pin "2") (pinfunction "S_2") (pintype "passive"))
      (node (ref "U8") (pin "3") (pinfunction "S_3") (pintype "passive"))
      (node (ref "U9") (pin "1") (pinfunction "S_1") (pintype "passive"))
      (node (ref "U9") (pin "2") (pinfunction "S_2") (pintype "passive"))
      (node (ref "U9") (pin "3") (pinfunction "S_3") (pintype "passive"))
    )
    (net (code "51") (name "Net-(C4-Pad1)") (class "Default")
      (node (ref "C4") (pin "1") (pinfunction "1_1") (pintype "passive"))
      (node (ref "R6") (pin "2") (pinfunction "2_2") (pintype "passive"))
    )
    (net (code "52") (name "Net-(C5-Pad1)") (class "Default")
      (node (ref "C5") (pin "1") (pinfunction "1_1") (pintype "passive"))
      (node (ref "R7") (pin "2") (pinfunction "2_2") (pintype "passive"))
    )
    (net (code "53") (name "Net-(C11-Pad2)") (class "Default")
      (node (ref "C11") (pin "2") (pinfunction "2_2") (pintype "passive"))
      (node (ref "L2") (pin "2") (pinfunction "2_2") (pintype "passive"))
      (node (ref "U3") (pin "1") (pinfunction "VSW_1") (pintype "power_in"))
      (node (ref "U3") (pin "12") (pinfunction "VSW_12") (pintype "power_in"))
      (node (ref "U3") (pin "13") (pinfunction "VSW_13") (pintype "power_in"))
      (node (ref "U3") (pin "16") (pinfunction "VSW_16") (pintype "passive"))
    )
    (net (code "54") (name "Net-(C18-Pad1)") (class "Default")
      (node (ref "C18") (pin "1") (pinfunction "1_1") (pintype "passive"))
      (node (ref "C22") (pin "1") (pinfunction "1_1") (pintype "passive"))
      (node (ref "R21") (pin "2") (pinfunction "2_2") (pintype "passive"))
      (node (ref "R25") (pin "1") (pinfunction "1_1") (pintype "passive"))
      (node (ref "U6") (pin "5") (pinfunction "D_5") (pintype "passive"))
      (node (ref "U6") (pin "6") (pinfunction "D_6") (pintype "passive"))
      (node (ref "U6") (pin "7") (pinfunction "D_7") (pintype "passive"))
      (node (ref "U6") (pin "8") (pinfunction "D_8") (pintype "passive"))
      (node (ref "U6") (pin "9") (pinfunction "D_9") (pintype "passive"))
    )
    (net (code "55") (name "Net-(C43-Pad2)") (class "Default")
      (node (ref "C43") (pin "2") (pinfunction "2_2") (pintype "passive"))
      (node (ref "C47") (pin "2") (pinfunction "2_2") (pintype "passive"))
      (node (ref "F1") (pin "2") (pinfunction "2_2") (pintype "passive"))
      (node (ref "R22") (pin "1") (pinfunction "1_1") (pintype "passive"))
      (node (ref "R26") (pin "1") (pinfunction "1_1") (pintype "passive"))
    )
    (net (code "56") (name "Net-(C44-Pad1)") (class "Default")
      (node (ref "C44") (pin "1") (pinfunction "1_1") (pintype "passive"))
      (node (ref "R23") (pin "1") (pinfunction "1_1") (pintype "passive"))
    )
    (net (code "57") (name "Net-(Q3-D)") (class "Default")
      (node (ref "F1") (pin "1") (pinfunction "1_1") (pintype "passive"))
      (node (ref "Q3") (pin "5_8") (pinfunction "D_5_8") (pintype "passive"))
    )
    (net (code "58") (name "Net-(R17-Pad2)") (class "Default")
      (node (ref "R17") (pin "2") (pinfunction "2_2") (pintype "passive"))
      (node (ref "R18") (pin "1") (pinfunction "1_1") (pintype "passive"))
    )
    (net (code "59") (name "Net-(U1-COMP1)") (class "Default")
      (node (ref "C3") (pin "1") (pinfunction "1_1") (pintype "passive"))
      (node (ref "R6") (pin "1") (pinfunction "1_1") (pintype "passive"))
      (node (ref "U1") (pin "16") (pinfunction "COMP1_16") (pintype "passive"))
    )
    (net (code "60") (name "Net-(U1-COMP2)") (class "Default")
      (node (ref "C6") (pin "1") (pinfunction "1_1") (pintype "passive"))
      (node (ref "R7") (pin "1") (pinfunction "1_1") (pintype "passive"))
      (node (ref "U1") (pin "17") (pinfunction "COMP2_17") (pintype "passive"))
    )
    (net (code "61") (name "Net-(U1-IADPT)") (class "Default")
      (node (ref "C10") (pin "1") (pinfunction "1_1") (pintype "passive"))
      (node (ref "R15") (pin "1") (pinfunction "1_1") (pintype "passive"))
      (node (ref "U1") (pin "8") (pinfunction "IADPT_8") (pintype "passive"))
    )
    (net (code "62") (name "Net-(U1-IBAT)") (class "Default")
      (node (ref "C8") (pin "1") (pinfunction "1_1") (pintype "passive"))
      (node (ref "U1") (pin "9") (pinfunction "IBAT_9") (pintype "passive"))
    )
    (net (code "63") (name "Net-(U1-PSYS)") (class "Default")
      (node (ref "R14") (pin "1") (pinfunction "1_1") (pintype "passive"))
      (node (ref "U1") (pin "10") (pinfunction "PSYS_10") (pintype "passive"))
    )
    (net (code "64") (name "Net-(U2-OUTN)") (class "Default")
      (node (ref "J5") (pin "1") (pinfunction "1_1") (pintype "passive"))
      (node (ref "L1") (pin "1") (pinfunction "1_1") (pintype "passive"))
      (node (ref "U2") (pin "10") (pinfunction "OUTN_10") (pintype "output"))
    )
    (net (code "65") (name "Net-(U2-OUTP)") (class "Default")
      (node (ref "J5") (pin "2") (pinfunction "2_2") (pintype "passive"))
      (node (ref "L1") (pin "2") (pinfunction "2_2") (pintype "passive"))
      (node (ref "U2") (pin "9") (pinfunction "OUTP_9") (pintype "output"))
    )
    (net (code "66") (name "Net-(U3-BST)") (class "Default")
      (node (ref "C11") (pin "1") (pinfunction "1_1") (pintype "passive"))
      (node (ref "U3") (pin "10") (pinfunction "BST_10") (pintype "passive"))
    )
    (net (code "67") (name "Net-(U5-GATE)") (class "Default")
      (node (ref "Q1") (pin "1") (pinfunction "1_1") (pintype "passive"))
      (node (ref "U5") (pin "5") (pinfunction "GATE_5") (pintype "passive"))
    )
    (net (code "68") (name "Net-(U5-VIN)") (class "Default")
      (node (ref "C1") (pin "2") (pinfunction "2_2") (pintype "passive"))
      (node (ref "U5") (pin "1") (pinfunction "VIN_1") (pintype "input"))
    )
    (net (code "69") (name "VSYS") (class "Default")
      (node (ref "C15") (pin "1") (pinfunction "1_1") (pintype "passive"))
      (node (ref "C19") (pin "2") (pinfunction "A_2") (pintype "passive"))
      (node (ref "C20") (pin "2") (pinfunction "A_2") (pintype "passive"))
      (node (ref "C24") (pin "1") (pinfunction "1_1") (pintype "passive"))
      (node (ref "C35") (pin "1") (pinfunction "1_1") (pintype "passive"))
      (node (ref "C36") (pin "1") (pinfunction "1_1") (pintype "passive"))
      (node (ref "C37") (pin "1") (pinfunction "1_1") (pintype "passive"))
      (node (ref "C38") (pin "1") (pinfunction "1_1") (pintype "passive"))
      (node (ref "C39") (pin "1") (pinfunction "1_1") (pintype "passive"))
      (node (ref "C40") (pin "1") (pinfunction "1_1") (pintype "passive"))
      (node (ref "C41") (pin "1") (pinfunction "1_1") (pintype "passive"))
      (node (ref "C42") (pin "1") (pinfunction "1_1") (pintype "passive"))
      (node (ref "Q3") (pin "1") (pinfunction "S_1") (pintype "passive"))
      (node (ref "Q3") (pin "2") (pinfunction "S_2") (pintype "passive"))
      (node (ref "Q3") (pin "3") (pinfunction "S_3") (pintype "passive"))
      (node (ref "U1") (pin "22") (pinfunction "VSYS_22") (pintype "passive"))
      (node (ref "U3") (pin "11") (pinfunction "VCC_11") (pintype "power_in"))
      (node (ref "U3") (pin "2") (pinfunction "VCC_2") (pintype "power_in"))
      (node (ref "U3") (pin "3") (pinfunction "VCC_3") (pintype "power_in"))
      (node (ref "U7") (pin "5") (pinfunction "D_5") (pintype "passive"))
      (node (ref "U7") (pin "6") (pinfunction "D_6") (pintype "passive"))
      (node (ref "U7") (pin "7") (pinfunction "D_7") (pintype "passive"))
      (node (ref "U7") (pin "8") (pinfunction "D_8") (pintype "passive"))
      (node (ref "U7") (pin "9") (pinfunction "D_9") (pintype "passive"))
    )
    (net (code "70") (name "unconnected-(U1-CMPIN-Pad14)") (class "Default")
      (node (ref "U1") (pin "14") (pinfunction "CMPIN_14") (pintype "passive"))
    )
    (net (code "71") (name "unconnected-(U2-N.C.-Pad5)") (class "Default")
      (node (ref "U2") (pin "5") (pinfunction "N.C._5") (pintype "passive"))
    )
    (net (code "72") (name "unconnected-(U2-N.C.-Pad6)") (class "Default")
      (node (ref "U2") (pin "6") (pinfunction "N.C._6") (pintype "passive"))
    )
    (net (code "73") (name "unconnected-(U2-N.C.-Pad12)") (class "Default")
      (node (ref "U2") (pin "12") (pinfunction "N.C._12") (pintype "passive"))
    )
    (net (code "74") (name "unconnected-(U2-N.C.-Pad13)") (class "Default")
      (node (ref "U2") (pin "13") (pinfunction "N.C._13") (pintype "passive"))
    )
    (net (code "75") (name "unconnected-(U3-EN{slash}SYNC-Pad9)") (class "Default")
      (node (ref "U3") (pin "9") (pinfunction "EN/SYNC_9") (pintype "passive"))
    )
    (net (code "76") (name "unconnected-(U3-PG-Pad8)") (class "Default")
      (node (ref "U3") (pin "8") (pinfunction "PG_8") (pintype "passive"))
    )
    (net (code "77") (name "unconnected-(U5-STAT-Pad4)") (class "Default")
      (node (ref "U5") (pin "4") (pinfunction "STAT_4") (pintype "output"))
    )
  )
)
